# 3_phase_sense.net
KiCad netlist of a schematic drawn in EAGLE
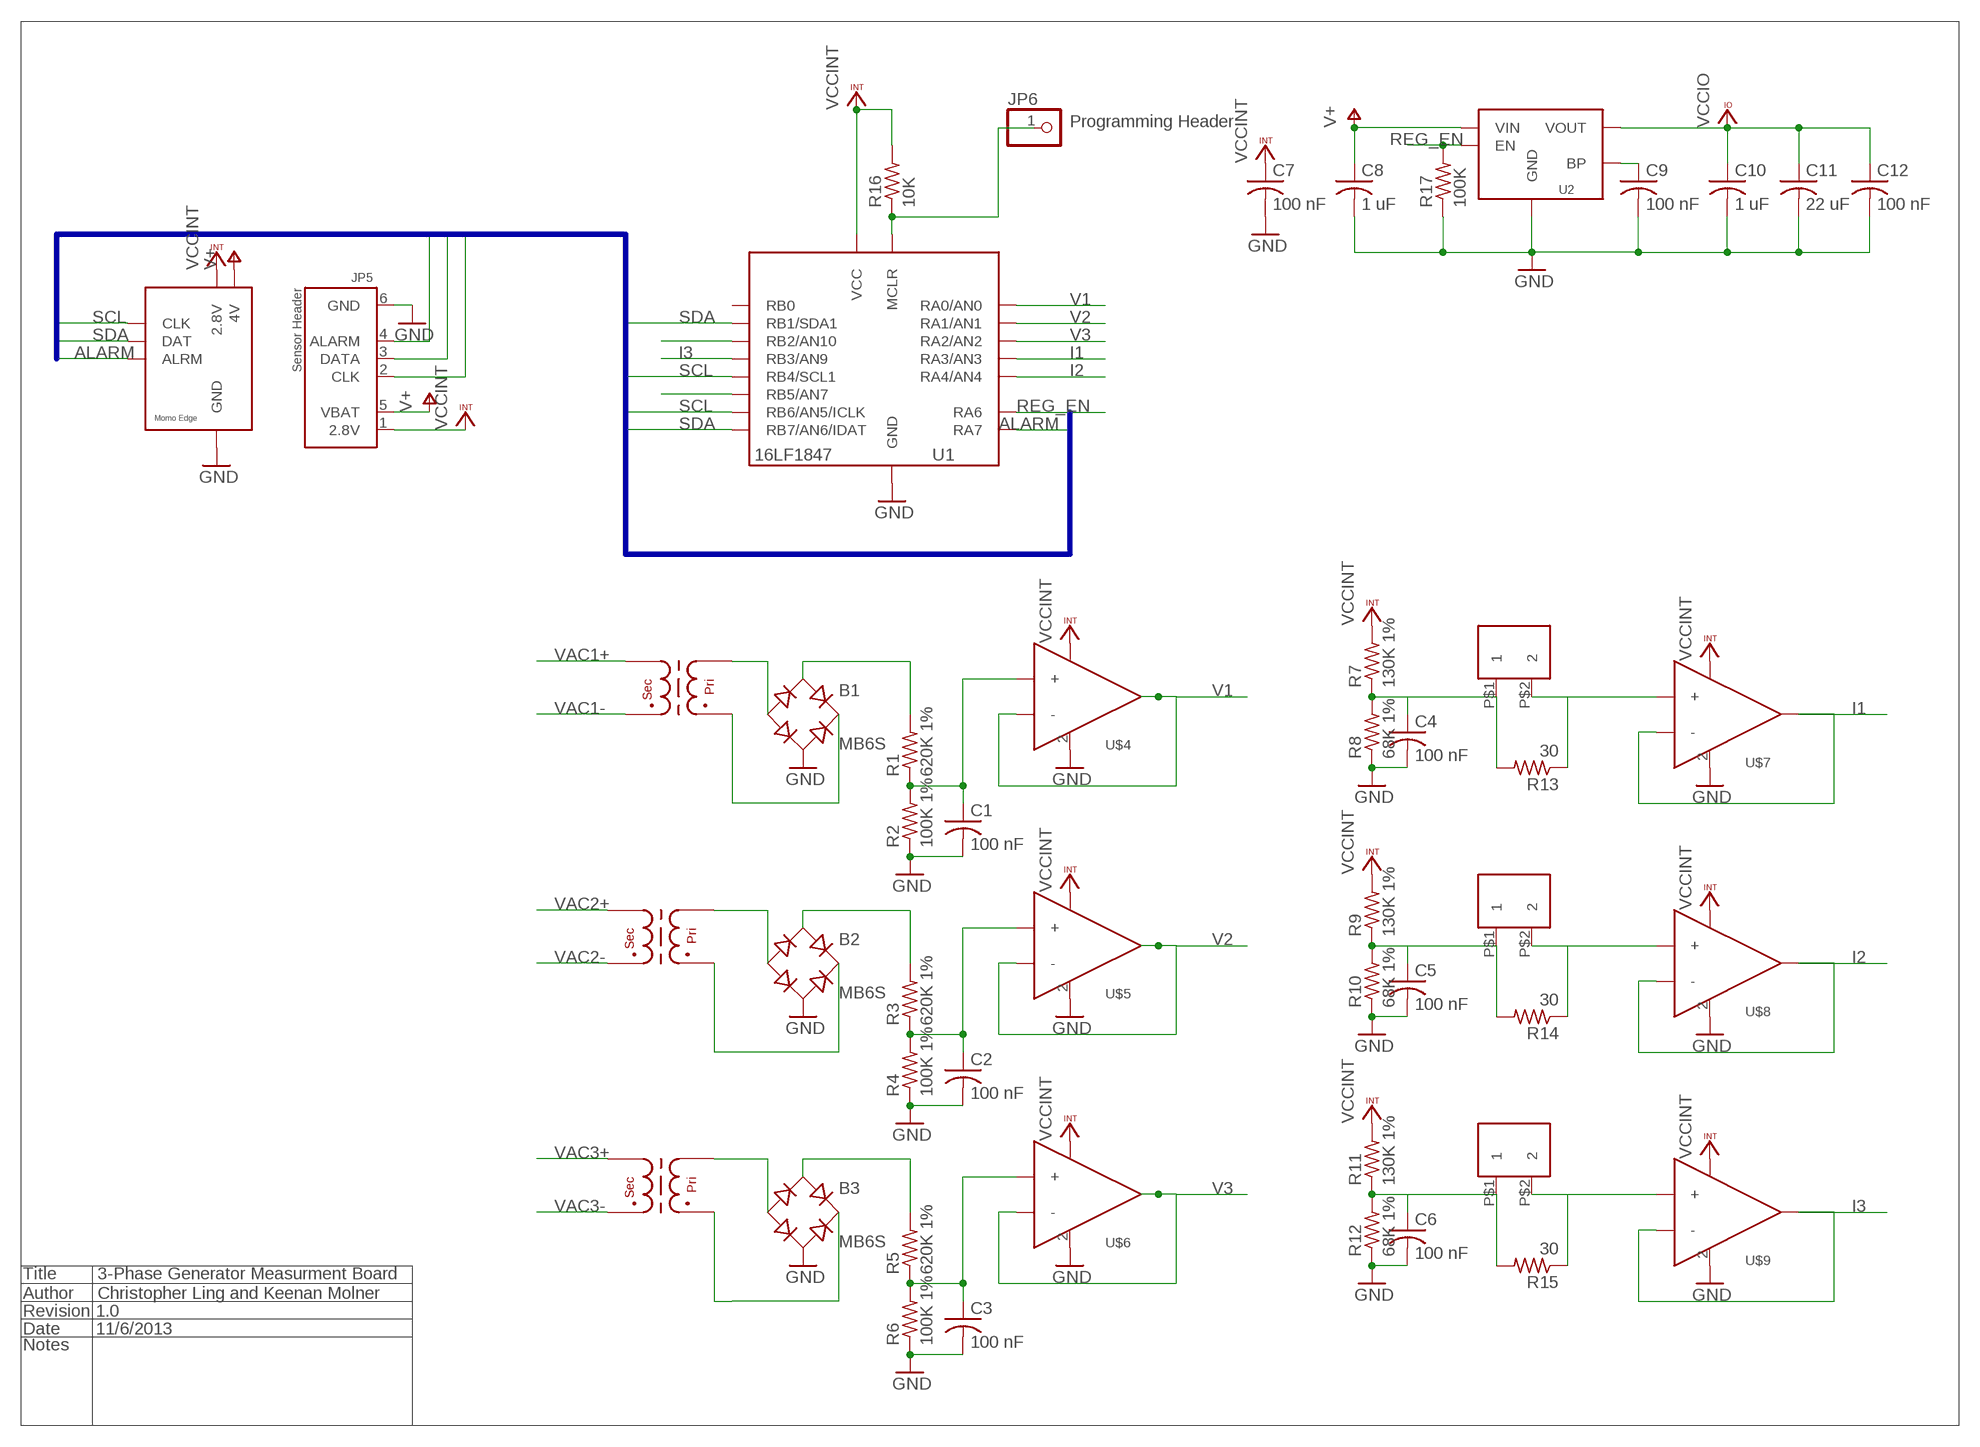
[diagram p0: schematic, sheet 1]

(export (version "E")
  (design (tool "Eeschema 10.0.6"))
  (components
    (comp (ref "B1")
      (value "MB6S")
      (footprint "eagle-import:SOIC-4")
      (libsource (lib "eagle-import") (part "MBS6"))
    )
    (comp (ref "B2")
      (value "MB6S")
      (footprint "eagle-import:SOIC-4")
      (libsource (lib "eagle-import") (part "MBS6"))
    )
    (comp (ref "B3")
      (value "MB6S")
      (footprint "eagle-import:SOIC-4")
      (libsource (lib "eagle-import") (part "MBS6"))
    )
    (comp (ref "C1")
      (value "100 nF")
      (footprint "eagle-import:C0402K")
      (libsource (lib "eagle-import") (part "C-USC0402K"))
    )
    (comp (ref "C2")
      (value "100 nF")
      (footprint "eagle-import:C0402K")
      (libsource (lib "eagle-import") (part "C-USC0402K"))
    )
    (comp (ref "C3")
      (value "100 nF")
      (footprint "eagle-import:C0402K")
      (libsource (lib "eagle-import") (part "C-USC0402K"))
    )
    (comp (ref "C4")
      (value "100 nF")
      (footprint "eagle-import:C0402K")
      (libsource (lib "eagle-import") (part "C-USC0402K"))
    )
    (comp (ref "C5")
      (value "100 nF")
      (footprint "eagle-import:C0402K")
      (libsource (lib "eagle-import") (part "C-USC0402K"))
    )
    (comp (ref "C6")
      (value "100 nF")
      (footprint "eagle-import:C0402K")
      (libsource (lib "eagle-import") (part "C-USC0402K"))
    )
    (comp (ref "C7")
      (value "100 nF")
      (footprint "eagle-import:C0402K")
      (libsource (lib "eagle-import") (part "C-USC0402K"))
    )
    (comp (ref "C8")
      (value "1 uF")
      (footprint "eagle-import:C0402K")
      (libsource (lib "eagle-import") (part "C-USC0402K"))
    )
    (comp (ref "C9")
      (value "100 nF")
      (footprint "eagle-import:C0402K")
      (libsource (lib "eagle-import") (part "C-USC0402K"))
    )
    (comp (ref "C10")
      (value "1 uF")
      (footprint "eagle-import:C0402K")
      (libsource (lib "eagle-import") (part "C-USC0402K"))
    )
    (comp (ref "C11")
      (value "22 uF")
      (footprint "eagle-import:C1206K")
      (libsource (lib "eagle-import") (part "C-USC1206K"))
    )
    (comp (ref "C12")
      (value "100 nF")
      (footprint "eagle-import:C0402K")
      (libsource (lib "eagle-import") (part "C-USC0402K"))
    )
    (comp (ref "JP1")
      (value "5MM-SCREWTERM-2POS")
      (footprint "eagle-import:5MM-SCREWTERM")
      (libsource (lib "eagle-import") (part "5MM-SCREWTERM-2POS"))
    )
    (comp (ref "JP2")
      (value "5MM-SCREWTERM-2POS")
      (footprint "eagle-import:5MM-SCREWTERM")
      (libsource (lib "eagle-import") (part "5MM-SCREWTERM-2POS"))
    )
    (comp (ref "JP3")
      (value "5MM-SCREWTERM-2POS")
      (footprint "eagle-import:5MM-SCREWTERM")
      (libsource (lib "eagle-import") (part "5MM-SCREWTERM-2POS"))
    )
    (comp (ref "JP4")
      (value "MOMO-VERT-6M")
      (footprint "eagle-import:1X06")
      (libsource (lib "eagle-import") (part "MOMO-VERT-6M"))
    )
    (comp (ref "JP5")
      (value "MOMO-SENSOR-RJ11")
      (footprint "eagle-import:RJ-12")
      (libsource (lib "eagle-import") (part "MOMO-SENSOR-RJ11"))
    )
    (comp (ref "JP6")
      (value "PINHD-1X1")
      (footprint "eagle-import:1X01")
      (libsource (lib "eagle-import") (part "PINHD-1X1"))
    )
    (comp (ref "R1")
      (value "620K 1%")
      (footprint "eagle-import:R0603")
      (libsource (lib "eagle-import") (part "R-US_R0603"))
    )
    (comp (ref "R2")
      (value "100K 1%")
      (footprint "eagle-import:R0603")
      (libsource (lib "eagle-import") (part "R-US_R0603"))
    )
    (comp (ref "R3")
      (value "620K 1%")
      (footprint "eagle-import:R0603")
      (libsource (lib "eagle-import") (part "R-US_R0603"))
    )
    (comp (ref "R4")
      (value "100K 1%")
      (footprint "eagle-import:R0603")
      (libsource (lib "eagle-import") (part "R-US_R0603"))
    )
    (comp (ref "R5")
      (value "620K 1%")
      (footprint "eagle-import:R0603")
      (libsource (lib "eagle-import") (part "R-US_R0603"))
    )
    (comp (ref "R6")
      (value "100K 1%")
      (footprint "eagle-import:R0603")
      (libsource (lib "eagle-import") (part "R-US_R0603"))
    )
    (comp (ref "R7")
      (value "130K 1%")
      (footprint "eagle-import:R0603")
      (libsource (lib "eagle-import") (part "R-US_R0603"))
    )
    (comp (ref "R8")
      (value "68K 1%")
      (footprint "eagle-import:R0603")
      (libsource (lib "eagle-import") (part "R-US_R0603"))
    )
    (comp (ref "R9")
      (value "130K 1%")
      (footprint "eagle-import:R0603")
      (libsource (lib "eagle-import") (part "R-US_R0603"))
    )
    (comp (ref "R10")
      (value "68K 1%")
      (footprint "eagle-import:R0603")
      (libsource (lib "eagle-import") (part "R-US_R0603"))
    )
    (comp (ref "R11")
      (value "130K 1%")
      (footprint "eagle-import:R0603")
      (libsource (lib "eagle-import") (part "R-US_R0603"))
    )
    (comp (ref "R12")
      (value "68K 1%")
      (footprint "eagle-import:R0603")
      (libsource (lib "eagle-import") (part "R-US_R0603"))
    )
    (comp (ref "R13")
      (value "30")
      (footprint "eagle-import:R2512")
      (libsource (lib "eagle-import") (part "R-US_R2512"))
    )
    (comp (ref "R14")
      (value "30")
      (footprint "eagle-import:R2512")
      (libsource (lib "eagle-import") (part "R-US_R2512"))
    )
    (comp (ref "R15")
      (value "30")
      (footprint "eagle-import:R2512")
      (libsource (lib "eagle-import") (part "R-US_R2512"))
    )
    (comp (ref "R16")
      (value "10K")
      (footprint "eagle-import:R0603")
      (libsource (lib "eagle-import") (part "R-US_R0603"))
    )
    (comp (ref "R17")
      (value "100K")
      (footprint "eagle-import:R0603")
      (libsource (lib "eagle-import") (part "R-US_R0603"))
    )
    (comp (ref "U$1")
      (value "CJ5143-AL")
      (footprint "eagle-import:CJ5143-AL")
      (libsource (lib "eagle-import") (part "CJ5143-AL"))
    )
    (comp (ref "U$2")
      (value "CJ5143-AL")
      (footprint "eagle-import:CJ5143-AL")
      (libsource (lib "eagle-import") (part "CJ5143-AL"))
    )
    (comp (ref "U$3")
      (value "CJ5143-AL")
      (footprint "eagle-import:CJ5143-AL")
      (libsource (lib "eagle-import") (part "CJ5143-AL"))
    )
    (comp (ref "U$4")
      (value "NJU7011F")
      (footprint "eagle-import:SOT23-5L")
      (libsource (lib "eagle-import") (part "NJU7011F"))
    )
    (comp (ref "U$5")
      (value "NJU7011F")
      (footprint "eagle-import:SOT23-5L")
      (libsource (lib "eagle-import") (part "NJU7011F"))
    )
    (comp (ref "U$6")
      (value "NJU7011F")
      (footprint "eagle-import:SOT23-5L")
      (libsource (lib "eagle-import") (part "NJU7011F"))
    )
    (comp (ref "U$7")
      (value "NJU7011F")
      (footprint "eagle-import:SOT23-5L")
      (libsource (lib "eagle-import") (part "NJU7011F"))
    )
    (comp (ref "U$8")
      (value "NJU7011F")
      (footprint "eagle-import:SOT23-5L")
      (libsource (lib "eagle-import") (part "NJU7011F"))
    )
    (comp (ref "U$9")
      (value "NJU7011F")
      (footprint "eagle-import:SOT23-5L")
      (libsource (lib "eagle-import") (part "NJU7011F"))
    )
    (comp (ref "U1")
      (value "PIC1847")
      (footprint "eagle-import:SSOP20")
      (libsource (lib "eagle-import") (part "PIC1847"))
    )
    (comp (ref "U2")
      (value "AP7115-LDO")
      (footprint "eagle-import:SOT353")
      (libsource (lib "eagle-import") (part "AP7115-LDO"))
    )
  )
  (nets
    (net (code "1") (name "/ALARM") (class "Default")
      (node (ref "JP4") (pin "5") (pinfunction "ALRM_5") (pintype "bidirectional"))
      (node (ref "JP5") (pin "4") (pinfunction "ALARM_4") (pintype "bidirectional"))
      (node (ref "U1") (pin "17") (pinfunction "RA7_17") (pintype "bidirectional"))
    )
    (net (code "2") (name "/I1") (class "Default")
      (node (ref "U$7") (pin "3") (pinfunction "-_3") (pintype "input"))
      (node (ref "U$7") (pin "5") (pinfunction "OUT_5") (pintype "output"))
      (node (ref "U1") (pin "2") (pinfunction "RA3/AN3_2") (pintype "bidirectional"))
    )
    (net (code "3") (name "/I2") (class "Default")
      (node (ref "U$8") (pin "3") (pinfunction "-_3") (pintype "input"))
      (node (ref "U$8") (pin "5") (pinfunction "OUT_5") (pintype "output"))
      (node (ref "U1") (pin "3") (pinfunction "RA4/AN4_3") (pintype "bidirectional"))
    )
    (net (code "4") (name "/I3") (class "Default")
      (node (ref "U$9") (pin "3") (pinfunction "-_3") (pintype "input"))
      (node (ref "U$9") (pin "5") (pinfunction "OUT_5") (pintype "output"))
      (node (ref "U1") (pin "10") (pinfunction "RB3/AN9_10") (pintype "bidirectional"))
    )
    (net (code "5") (name "/REG_EN") (class "Default")
      (node (ref "R17") (pin "2") (pinfunction "2_2") (pintype "passive"))
      (node (ref "U1") (pin "18") (pinfunction "RA6_18") (pintype "bidirectional"))
      (node (ref "U2") (pin "3") (pinfunction "EN_3") (pintype "power_in"))
    )
    (net (code "6") (name "/SCL") (class "Default")
      (node (ref "JP4") (pin "3") (pinfunction "CLK_3") (pintype "bidirectional"))
      (node (ref "JP5") (pin "2") (pinfunction "CLK_2") (pintype "bidirectional"))
      (node (ref "U1") (pin "11") (pinfunction "RB4/SCL1_11") (pintype "bidirectional"))
      (node (ref "U1") (pin "13") (pinfunction "RB6/AN5/ICLK_13") (pintype "bidirectional"))
    )
    (net (code "7") (name "/SDA") (class "Default")
      (node (ref "JP4") (pin "4") (pinfunction "DAT_4") (pintype "bidirectional"))
      (node (ref "JP5") (pin "3") (pinfunction "DATA_3") (pintype "bidirectional"))
      (node (ref "U1") (pin "14") (pinfunction "RB7/AN6/IDAT_14") (pintype "bidirectional"))
      (node (ref "U1") (pin "8") (pinfunction "RB1/SDA1_8") (pintype "bidirectional"))
    )
    (net (code "8") (name "/V1") (class "Default")
      (node (ref "U$4") (pin "3") (pinfunction "-_3") (pintype "input"))
      (node (ref "U$4") (pin "5") (pinfunction "OUT_5") (pintype "output"))
      (node (ref "U1") (pin "19") (pinfunction "RA0/AN0_19") (pintype "bidirectional"))
    )
    (net (code "9") (name "/V2") (class "Default")
      (node (ref "C4") (pin "1") (pinfunction "1_1") (pintype "passive"))
      (node (ref "JP1") (pin "P$1") (pinfunction "1_P$1") (pintype "passive"))
      (node (ref "R13") (pin "2") (pinfunction "2_2") (pintype "passive"))
      (node (ref "R7") (pin "1") (pinfunction "1_1") (pintype "passive"))
      (node (ref "R8") (pin "2") (pinfunction "2_2") (pintype "passive"))
      (node (ref "U$5") (pin "3") (pinfunction "-_3") (pintype "input"))
      (node (ref "U$5") (pin "5") (pinfunction "OUT_5") (pintype "output"))
      (node (ref "U1") (pin "20") (pinfunction "RA1/AN1_20") (pintype "bidirectional"))
    )
    (net (code "10") (name "/V3") (class "Default")
      (node (ref "U$6") (pin "3") (pinfunction "-_3") (pintype "input"))
      (node (ref "U$6") (pin "5") (pinfunction "OUT_5") (pintype "output"))
      (node (ref "U1") (pin "1") (pinfunction "RA2/AN2_1") (pintype "bidirectional"))
    )
    (net (code "11") (name "/VAC1+") (class "Default")
      (node (ref "U$1") (pin "P$5") (pinfunction "P$5_P$5") (pintype "passive"))
    )
    (net (code "12") (name "/VAC1-") (class "Default")
      (node (ref "U$1") (pin "P$6") (pinfunction "P$6_P$6") (pintype "passive"))
    )
    (net (code "13") (name "/VAC2+") (class "Default")
      (node (ref "U$2") (pin "P$5") (pinfunction "P$5_P$5") (pintype "passive"))
    )
    (net (code "14") (name "/VAC2-") (class "Default")
      (node (ref "U$2") (pin "P$6") (pinfunction "P$6_P$6") (pintype "passive"))
    )
    (net (code "15") (name "/VAC3+") (class "Default")
      (node (ref "U$3") (pin "P$5") (pinfunction "P$5_P$5") (pintype "passive"))
    )
    (net (code "16") (name "/VAC3-") (class "Default")
      (node (ref "U$3") (pin "P$6") (pinfunction "P$6_P$6") (pintype "passive"))
    )
    (net (code "17") (name "GND") (class "Default")
      (node (ref "B1") (pin "~2") (pinfunction "AC2_~2") (pintype "passive"))
      (node (ref "B2") (pin "~2") (pinfunction "AC2_~2") (pintype "passive"))
      (node (ref "B3") (pin "~2") (pinfunction "AC2_~2") (pintype "passive"))
      (node (ref "C1") (pin "2") (pinfunction "2_2") (pintype "passive"))
      (node (ref "C10") (pin "2") (pinfunction "2_2") (pintype "passive"))
      (node (ref "C11") (pin "2") (pinfunction "2_2") (pintype "passive"))
      (node (ref "C12") (pin "2") (pinfunction "2_2") (pintype "passive"))
      (node (ref "C2") (pin "2") (pinfunction "2_2") (pintype "passive"))
      (node (ref "C3") (pin "2") (pinfunction "2_2") (pintype "passive"))
      (node (ref "C4") (pin "2") (pinfunction "2_2") (pintype "passive"))
      (node (ref "C5") (pin "2") (pinfunction "2_2") (pintype "passive"))
      (node (ref "C6") (pin "2") (pinfunction "2_2") (pintype "passive"))
      (node (ref "C7") (pin "2") (pinfunction "2_2") (pintype "passive"))
      (node (ref "C8") (pin "2") (pinfunction "2_2") (pintype "passive"))
      (node (ref "C9") (pin "2") (pinfunction "2_2") (pintype "passive"))
      (node (ref "JP4") (pin "7") (pinfunction "GND_7") (pintype "power_in"))
      (node (ref "JP5") (pin "6") (pinfunction "GND_6") (pintype "bidirectional"))
      (node (ref "R10") (pin "1") (pinfunction "1_1") (pintype "passive"))
      (node (ref "R12") (pin "1") (pinfunction "1_1") (pintype "passive"))
      (node (ref "R17") (pin "1") (pinfunction "1_1") (pintype "passive"))
      (node (ref "R2") (pin "1") (pinfunction "1_1") (pintype "passive"))
      (node (ref "R4") (pin "1") (pinfunction "1_1") (pintype "passive"))
      (node (ref "R6") (pin "1") (pinfunction "1_1") (pintype "passive"))
      (node (ref "R8") (pin "1") (pinfunction "1_1") (pintype "passive"))
      (node (ref "U$4") (pin "2") (pinfunction "VSS_2") (pintype "power_in"))
      (node (ref "U$5") (pin "2") (pinfunction "VSS_2") (pintype "power_in"))
      (node (ref "U$6") (pin "2") (pinfunction "VSS_2") (pintype "power_in"))
      (node (ref "U$7") (pin "2") (pinfunction "VSS_2") (pintype "power_in"))
      (node (ref "U$8") (pin "2") (pinfunction "VSS_2") (pintype "power_in"))
      (node (ref "U$9") (pin "2") (pinfunction "VSS_2") (pintype "power_in"))
      (node (ref "U1") (pin "15") (pinfunction "GND_15") (pintype "power_in"))
      (node (ref "U1") (pin "16") (pinfunction "GND_16") (pintype "power_in"))
      (node (ref "U2") (pin "2") (pinfunction "GND_2") (pintype "power_in"))
    )
    (net (code "18") (name "Net-(B1-AC1)") (class "Default")
      (node (ref "B1") (pin "~1") (pinfunction "AC1_~1") (pintype "passive"))
      (node (ref "R1") (pin "2") (pinfunction "2_2") (pintype "passive"))
    )
    (net (code "19") (name "Net-(B1-Pad+)") (class "Default")
      (node (ref "B1") (pin "+") (pinfunction "+_+") (pintype "passive"))
      (node (ref "U$1") (pin "P$1") (pinfunction "P$1_P$1") (pintype "passive"))
    )
    (net (code "20") (name "Net-(B1-Pad-)") (class "Default")
      (node (ref "B1") (pin "-") (pinfunction "-_-") (pintype "passive"))
      (node (ref "U$1") (pin "P$4") (pinfunction "P$4_P$4") (pintype "passive"))
    )
    (net (code "21") (name "Net-(B2-AC1)") (class "Default")
      (node (ref "B2") (pin "~1") (pinfunction "AC1_~1") (pintype "passive"))
      (node (ref "R3") (pin "2") (pinfunction "2_2") (pintype "passive"))
    )
    (net (code "22") (name "Net-(B2-Pad+)") (class "Default")
      (node (ref "B2") (pin "+") (pinfunction "+_+") (pintype "passive"))
      (node (ref "U$2") (pin "P$1") (pinfunction "P$1_P$1") (pintype "passive"))
    )
    (net (code "23") (name "Net-(B2-Pad-)") (class "Default")
      (node (ref "B2") (pin "-") (pinfunction "-_-") (pintype "passive"))
      (node (ref "U$2") (pin "P$4") (pinfunction "P$4_P$4") (pintype "passive"))
    )
    (net (code "24") (name "Net-(B3-AC1)") (class "Default")
      (node (ref "B3") (pin "~1") (pinfunction "AC1_~1") (pintype "passive"))
      (node (ref "R5") (pin "2") (pinfunction "2_2") (pintype "passive"))
    )
    (net (code "25") (name "Net-(B3-Pad+)") (class "Default")
      (node (ref "B3") (pin "+") (pinfunction "+_+") (pintype "passive"))
      (node (ref "U$3") (pin "P$1") (pinfunction "P$1_P$1") (pintype "passive"))
    )
    (net (code "26") (name "Net-(B3-Pad-)") (class "Default")
      (node (ref "B3") (pin "-") (pinfunction "-_-") (pintype "passive"))
      (node (ref "U$3") (pin "P$4") (pinfunction "P$4_P$4") (pintype "passive"))
    )
    (net (code "27") (name "Net-(JP1-2)") (class "Default")
      (node (ref "JP1") (pin "P$2") (pinfunction "2_P$2") (pintype "passive"))
      (node (ref "R13") (pin "1") (pinfunction "1_1") (pintype "passive"))
      (node (ref "U$7") (pin "1") (pinfunction "+_1") (pintype "input"))
    )
    (net (code "28") (name "Net-(JP2-1)") (class "Default")
      (node (ref "C5") (pin "1") (pinfunction "1_1") (pintype "passive"))
      (node (ref "JP2") (pin "P$1") (pinfunction "1_P$1") (pintype "passive"))
      (node (ref "R10") (pin "2") (pinfunction "2_2") (pintype "passive"))
      (node (ref "R14") (pin "2") (pinfunction "2_2") (pintype "passive"))
      (node (ref "R9") (pin "1") (pinfunction "1_1") (pintype "passive"))
    )
    (net (code "29") (name "Net-(JP2-2)") (class "Default")
      (node (ref "JP2") (pin "P$2") (pinfunction "2_P$2") (pintype "passive"))
      (node (ref "R14") (pin "1") (pinfunction "1_1") (pintype "passive"))
      (node (ref "U$8") (pin "1") (pinfunction "+_1") (pintype "input"))
    )
    (net (code "30") (name "Net-(JP3-1)") (class "Default")
      (node (ref "C6") (pin "1") (pinfunction "1_1") (pintype "passive"))
      (node (ref "JP3") (pin "P$1") (pinfunction "1_P$1") (pintype "passive"))
      (node (ref "R11") (pin "1") (pinfunction "1_1") (pintype "passive"))
      (node (ref "R12") (pin "2") (pinfunction "2_2") (pintype "passive"))
      (node (ref "R15") (pin "2") (pinfunction "2_2") (pintype "passive"))
    )
    (net (code "31") (name "Net-(JP3-2)") (class "Default")
      (node (ref "JP3") (pin "P$2") (pinfunction "2_P$2") (pintype "passive"))
      (node (ref "R15") (pin "1") (pinfunction "1_1") (pintype "passive"))
      (node (ref "U$9") (pin "1") (pinfunction "+_1") (pintype "input"))
    )
    (net (code "32") (name "Net-(U$4-+)") (class "Default")
      (node (ref "C1") (pin "1") (pinfunction "1_1") (pintype "passive"))
      (node (ref "R1") (pin "1") (pinfunction "1_1") (pintype "passive"))
      (node (ref "R2") (pin "2") (pinfunction "2_2") (pintype "passive"))
      (node (ref "U$4") (pin "1") (pinfunction "+_1") (pintype "input"))
    )
    (net (code "33") (name "Net-(U$5-+)") (class "Default")
      (node (ref "C2") (pin "1") (pinfunction "1_1") (pintype "passive"))
      (node (ref "R3") (pin "1") (pinfunction "1_1") (pintype "passive"))
      (node (ref "R4") (pin "2") (pinfunction "2_2") (pintype "passive"))
      (node (ref "U$5") (pin "1") (pinfunction "+_1") (pintype "input"))
    )
    (net (code "34") (name "Net-(U$6-+)") (class "Default")
      (node (ref "C3") (pin "1") (pinfunction "1_1") (pintype "passive"))
      (node (ref "R5") (pin "1") (pinfunction "1_1") (pintype "passive"))
      (node (ref "R6") (pin "2") (pinfunction "2_2") (pintype "passive"))
      (node (ref "U$6") (pin "1") (pinfunction "+_1") (pintype "input"))
    )
    (net (code "35") (name "Net-(U1-MCLR)") (class "Default")
      (node (ref "JP6") (pin "1") (pinfunction "1_1") (pintype "passive"))
      (node (ref "R16") (pin "1") (pinfunction "1_1") (pintype "passive"))
      (node (ref "U1") (pin "4") (pinfunction "MCLR_4") (pintype "bidirectional"))
    )
    (net (code "36") (name "Net-(U2-BP)") (class "Default")
      (node (ref "C9") (pin "1") (pinfunction "1_1") (pintype "passive"))
      (node (ref "U2") (pin "4") (pinfunction "BP_4") (pintype "power_in"))
    )
    (net (code "37") (name "V+") (class "Default")
      (node (ref "C8") (pin "1") (pinfunction "1_1") (pintype "passive"))
      (node (ref "JP4") (pin "6") (pinfunction "4V_6") (pintype "power_in"))
      (node (ref "JP5") (pin "5") (pinfunction "VBAT_5") (pintype "bidirectional"))
      (node (ref "U2") (pin "1") (pinfunction "VIN_1") (pintype "power_in"))
    )
    (net (code "38") (name "VCCINT") (class "Default")
      (node (ref "C7") (pin "1") (pinfunction "1_1") (pintype "passive"))
      (node (ref "JP4") (pin "1") (pinfunction "2.8V_1") (pintype "power_in"))
      (node (ref "JP5") (pin "1") (pinfunction "2.8V_1") (pintype "bidirectional"))
      (node (ref "R11") (pin "2") (pinfunction "2_2") (pintype "passive"))
      (node (ref "R16") (pin "2") (pinfunction "2_2") (pintype "passive"))
      (node (ref "R7") (pin "2") (pinfunction "2_2") (pintype "passive"))
      (node (ref "R9") (pin "2") (pinfunction "2_2") (pintype "passive"))
      (node (ref "U$4") (pin "4") (pinfunction "VDD_4") (pintype "power_in"))
      (node (ref "U$5") (pin "4") (pinfunction "VDD_4") (pintype "power_in"))
      (node (ref "U$6") (pin "4") (pinfunction "VDD_4") (pintype "power_in"))
      (node (ref "U$7") (pin "4") (pinfunction "VDD_4") (pintype "power_in"))
      (node (ref "U$8") (pin "4") (pinfunction "VDD_4") (pintype "power_in"))
      (node (ref "U$9") (pin "4") (pinfunction "VDD_4") (pintype "power_in"))
      (node (ref "U1") (pin "5") (pinfunction "VCC_5") (pintype "power_in"))
      (node (ref "U1") (pin "6") (pinfunction "VCC_6") (pintype "power_in"))
    )
    (net (code "39") (name "VCCIO") (class "Default")
      (node (ref "C10") (pin "1") (pinfunction "1_1") (pintype "passive"))
      (node (ref "C11") (pin "1") (pinfunction "1_1") (pintype "passive"))
      (node (ref "C12") (pin "1") (pinfunction "1_1") (pintype "passive"))
      (node (ref "U2") (pin "5") (pinfunction "VOUT_5") (pintype "power_in"))
    )
    (net (code "40") (name "unconnected-(U1-RB0-Pad7)") (class "Default")
      (node (ref "U1") (pin "7") (pinfunction "RB0_7") (pintype "bidirectional"))
    )
    (net (code "41") (name "unconnected-(U1-RB2{slash}AN10-Pad9)") (class "Default")
      (node (ref "U1") (pin "9") (pinfunction "RB2/AN10_9") (pintype "bidirectional"))
    )
    (net (code "42") (name "unconnected-(U1-RB5{slash}AN7-Pad12)") (class "Default")
      (node (ref "U1") (pin "12") (pinfunction "RB5/AN7_12") (pintype "bidirectional"))
    )
  )
)
